# 04-LCD.net
KiCad netlist of a schematic drawn in Altium Designer
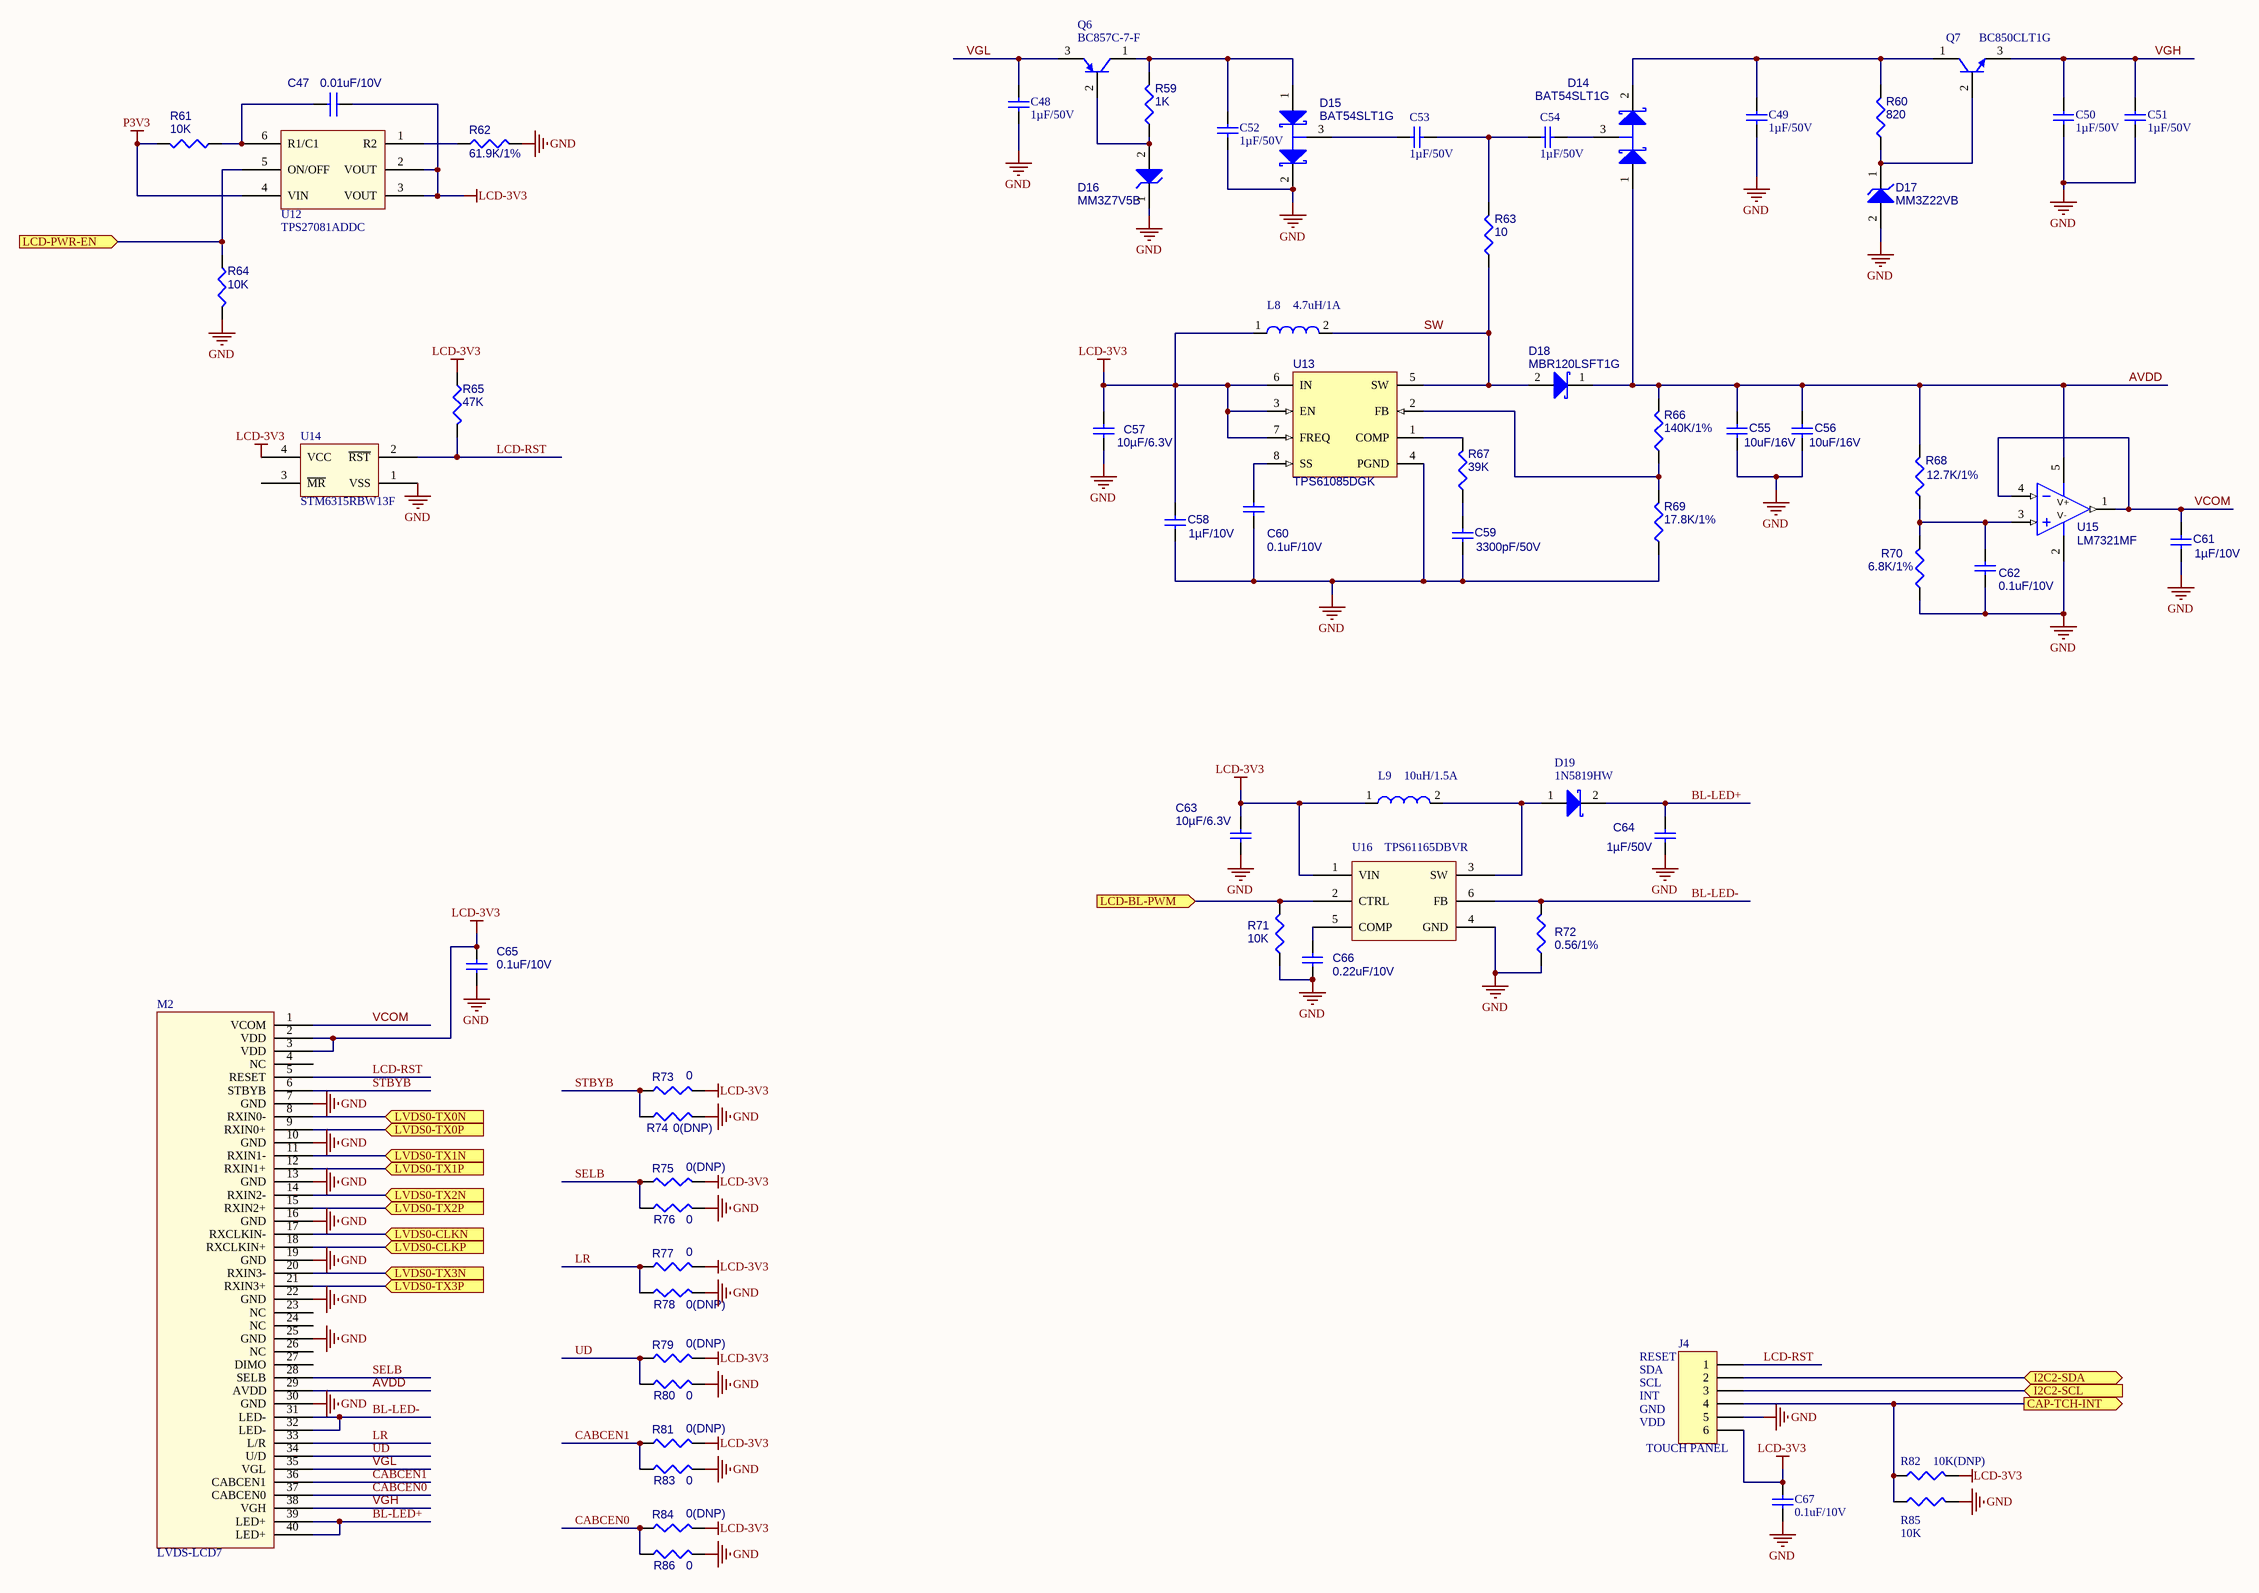
[diagram p0: 04-LCD.SchDoc]

(export (version "E")
  (design (tool "Eeschema 10.0.6"))
  (components
    (comp (ref "C47") (value "0.01uF/10V") (footprint "0402") (libsource (lib "*") (part "P_CAP NP")))
    (comp (ref "C48")
      (value "1µF/50V")
      (footprint "0603")
      (description "Capacitor")
      (fields (field (name "PUBLISHER") "Altium Limited"))
      (libsource (lib "Miscellaneous Devices") (part "Cap"))
    )
    (comp (ref "C49")
      (value "1µF/50V")
      (footprint "0603")
      (description "Capacitor")
      (fields (field (name "PUBLISHER") "Altium Limited"))
      (libsource (lib "Miscellaneous Devices") (part "Cap"))
    )
    (comp (ref "C50")
      (value "1µF/50V")
      (footprint "0603")
      (description "Capacitor")
      (fields (field (name "PUBLISHER") "Altium Limited"))
      (libsource (lib "Miscellaneous Devices") (part "Cap"))
    )
    (comp (ref "C51")
      (value "1µF/50V")
      (footprint "0603")
      (description "Capacitor")
      (fields (field (name "PUBLISHER") "Altium Limited"))
      (libsource (lib "Miscellaneous Devices") (part "Cap"))
    )
    (comp (ref "C52")
      (value "1µF/50V")
      (footprint "0603")
      (description "Capacitor")
      (fields (field (name "PUBLISHER") "Altium Limited"))
      (libsource (lib "Miscellaneous Devices") (part "Cap"))
    )
    (comp (ref "C53")
      (value "1µF/50V")
      (footprint "0603")
      (description "Capacitor")
      (fields (field (name "PUBLISHER") "Altium Limited"))
      (libsource (lib "Miscellaneous Devices") (part "Cap"))
    )
    (comp (ref "C54")
      (value "1µF/50V")
      (footprint "0603")
      (description "Capacitor")
      (fields (field (name "PUBLISHER") "Altium Limited"))
      (libsource (lib "Miscellaneous Devices") (part "Cap"))
    )
    (comp (ref "C55")
      (value "10uF/16V")
      (footprint "0805")
      (description "CAP, CERM, 10 µF, 25 V, +/- 10%, X5R, 0805")
      (fields
        (field (name "PARTNUMBER") "C2012X5R1E106K125AB")
        (field (name "MANUFACTURER") "TDK")
        (field (name "PUBLISHER") "Texas Instruments")
      )
      (libsource (lib "Capacitor_Ceramic") (part "C2012X5R1E106K125AB"))
    )
    (comp (ref "C56")
      (value "10uF/16V")
      (footprint "0805")
      (description "CAP, CERM, 10 µF, 25 V, +/- 10%, X5R, 0805")
      (fields
        (field (name "PARTNUMBER") "C2012X5R1E106K125AB")
        (field (name "MANUFACTURER") "TDK")
        (field (name "PUBLISHER") "Texas Instruments")
      )
      (libsource (lib "Capacitor_Ceramic") (part "C2012X5R1E106K125AB"))
    )
    (comp (ref "C57")
      (value "10µF/6.3V")
      (footprint "0805")
      (description "CAP, CERM, 10 µF, 10 V, +/- 10%, X5R, 0805")
      (fields
        (field (name "PARTNUMBER") "GRM219R61A106KE44D")
        (field (name "MANUFACTURER") "MuRata")
        (field (name "PUBLISHER") "Texas Instruments")
      )
      (libsource (lib "Capacitor_Ceramic") (part "GRM219R61A106KE44D"))
    )
    (comp (ref "C58")
      (value "1µF/10V")
      (footprint "0402")
      (description "CAP, CERM, 1 µF, 50 V, +/- 10%, X5R, 0603")
      (fields
        (field (name "PARTNUMBER") "GRM188R61H105KAALD")
        (field (name "MANUFACTURER") "MuRata")
        (field (name "PUBLISHER") "Texas Instruments")
      )
      (libsource (lib "Capacitor_Ceramic") (part "GRM188R61H105KAALD"))
    )
    (comp (ref "C59")
      (value "3300pF/50V")
      (footprint "0402")
      (description "CAP, CERM, 3300 pF, 50 V, +/- 10%, X7R, 0402")
      (fields
        (field (name "PARTNUMBER") "GRM155R71H332KA01D")
        (field (name "MANUFACTURER") "MuRata")
        (field (name "PUBLISHER") "Texas Instruments")
      )
      (libsource (lib "Capacitor_Ceramic") (part "GRM155R71H332KA01D"))
    )
    (comp (ref "C60")
      (value "0.1uF/10V")
      (footprint "0402")
      (description "CAP, CERM, 0.1 µF, 16 V, +/- 10%, X7R, 0402")
      (fields
        (field (name "PARTNUMBER") "GRM155R71C104KA88D")
        (field (name "MANUFACTURER") "MuRata")
        (field (name "PUBLISHER") "Texas Instruments")
      )
      (libsource (lib "Capacitor_Ceramic") (part "GRM155R71C104KA88D"))
    )
    (comp (ref "C61")
      (value "1µF/10V")
      (footprint "0402")
      (description "CAP, CERM, 1 µF, 50 V, +/- 10%, X5R, 0603")
      (fields
        (field (name "PARTNUMBER") "GRM188R61H105KAALD")
        (field (name "MANUFACTURER") "MuRata")
        (field (name "PUBLISHER") "Texas Instruments")
      )
      (libsource (lib "Capacitor_Ceramic") (part "GRM188R61H105KAALD"))
    )
    (comp (ref "C62")
      (value "0.1uF/10V")
      (footprint "0402")
      (description "CAP, CERM, 0.1 µF, 16 V, +/- 10%, X7R, 0402")
      (fields
        (field (name "PARTNUMBER") "GRM155R71C104KA88D")
        (field (name "MANUFACTURER") "MuRata")
        (field (name "PUBLISHER") "Texas Instruments")
      )
      (libsource (lib "Capacitor_Ceramic") (part "GRM155R71C104KA88D"))
    )
    (comp (ref "C63")
      (value "10µF/6.3V")
      (footprint "0805")
      (description "CAP, CERM, 10 µF, 10 V, +/- 10%, X5R, 0805")
      (fields
        (field (name "PARTNUMBER") "GRM219R61A106KE44D")
        (field (name "MANUFACTURER") "MuRata")
        (field (name "PUBLISHER") "Texas Instruments")
      )
      (libsource (lib "Capacitor_Ceramic") (part "GRM219R61A106KE44D"))
    )
    (comp (ref "C64")
      (value "1µF/50V")
      (footprint "0603")
      (description "CAP, CERM, 1 µF, 50 V, +/- 10%, X5R, 0603")
      (fields
        (field (name "PARTNUMBER") "GRM188R61H105KAALD")
        (field (name "MANUFACTURER") "MuRata")
        (field (name "PUBLISHER") "Texas Instruments")
      )
      (libsource (lib "Capacitor_Ceramic") (part "GRM188R61H105KAALD"))
    )
    (comp (ref "C65")
      (value "0.1uF/10V")
      (footprint "0402")
      (description "CAP, CERM, 0.1 µF, 16 V, +/- 10%, X7R, 0402")
      (fields
        (field (name "PARTNUMBER") "GRM155R71C104KA88D")
        (field (name "MANUFACTURER") "MuRata")
        (field (name "PUBLISHER") "Texas Instruments")
      )
      (libsource (lib "Capacitor_Ceramic") (part "GRM155R71C104KA88D"))
    )
    (comp (ref "C66")
      (value "0.22uF/10V")
      (footprint "0402")
      (description "CAP, CERM, 0.1 µF, 16 V, +/- 10%, X7R, 0402")
      (fields
        (field (name "PARTNUMBER") "GRM155R71C104KA88D")
        (field (name "MANUFACTURER") "MuRata")
        (field (name "PUBLISHER") "Texas Instruments")
      )
      (libsource (lib "Capacitor_Ceramic") (part "GRM155R71C104KA88D"))
    )
    (comp (ref "C67")
      (value "0.1uF/10V")
      (footprint "0402")
      (description "Capacitor")
      (fields (field (name "PUBLISHER") "Altium Limited"))
      (libsource (lib "Miscellaneous Devices") (part "Cap"))
    )
    (comp (ref "D14")
      (value "BAT54SLT1G")
      (footprint "SOT-23")
      (description "Diode, Schottky, 30 V, 0.2 A, SOT-23")
      (fields (field (name "MANUFACTURER") "ON Semiconductor") (field (name "PUBLISHER") "Texas Instruments"))
      (libsource (lib "Diode") (part "BAT54SLT1G"))
    )
    (comp (ref "D15")
      (value "BAT54SLT1G")
      (footprint "SOT-23")
      (description "Diode, Schottky, 30 V, 0.2 A, SOT-23")
      (fields (field (name "MANUFACTURER") "ON Semiconductor") (field (name "PUBLISHER") "Texas Instruments"))
      (libsource (lib "Diode") (part "BAT54SLT1G"))
    )
    (comp (ref "D16")
      (value "MM3Z7V5B")
      (footprint "SOD323F")
      (description "Diode, Zener, 7.5 V, 200 mW, SOD-323F")
      (fields
        (field (name "MANUFACTURER") "Fairchild Semiconductor")
        (field (name "SYMBOLCREATOR") "a0412235")
        (field (name "PUBLISHER") "Texas Instruments")
      )
      (libsource (lib "ZenerDiodes") (part "MM3Z7V5B"))
    )
    (comp (ref "D17")
      (value "MM3Z22VB")
      (footprint "SOD323F")
      (description "Diode, Zener, 18 V, 200 mW, SOD-323F")
      (fields
        (field (name "PARTNUMBER") "MM3Z18VB")
        (field (name "MANUFACTURER") "Fairchild Semiconductor")
        (field (name "SYMBOLCREATOR") "a0412235")
        (field (name "PUBLISHER") "Texas Instruments")
      )
      (libsource (lib "ZenerDiodes") (part "MM3Z18VB"))
    )
    (comp (ref "D18")
      (value "MBR120LSFT1G")
      (footprint "SOD123FL")
      (description "Diode, Schottky, 20 V, 1 A, SOD-123FL")
      (fields (field (name "MANUFACTURER") "ON Semiconductor") (field (name "PUBLISHER") "Texas Instruments"))
      (libsource (lib "Diode") (part "MBR120LSFT1G"))
    )
    (comp (ref "D19")
      (value "1N5819HW")
      (footprint "1N5819")
      (description "Schottky Rectifier")
      (libsource (lib "Miscellaneous Devices") (part "Diode 11DQ03"))
    )
    (comp (ref "J4")
      (value "TOUCH PANEL")
      (footprint "FPC0.5-DR-SMD-XP-F(6P)")
      (description "Header, 6-Pin")
      (fields (field (name "PUBLISHER") "Altium Limited"))
      (libsource (lib "Miscellaneous Connectors") (part "Header 6"))
    )
    (comp (ref "L8")
      (value "4.7uH/1A")
      (footprint "IND-4.7UH-1A")
      (description "IND PWR 4.7UH@1MHZ 1A 20% SMD")
      (fields (field (name "TOLERANCE") "20%"))
      (libsource (lib "*") (part "INDUCTOR"))
    )
    (comp (ref "L9")
      (value "10uH/1.5A")
      (footprint "IND-10UH-1.5A")
      (description "IND PWR 4.7UH@1MHZ 1A 20% SMD")
      (fields (field (name "TOLERANCE") "20%"))
      (libsource (lib "*") (part "INDUCTOR"))
    )
    (comp (ref "M2")
      (value "LVDS-LCD7")
      (footprint "FPC0.5-DR-SMD-XP-F(40P)")
      (libsource (lib "Schlib") (part "LVDS-LCD7"))
    )
    (comp (ref "Q6")
      (value "BC857C-7-F")
      (footprint "NPN")
      (description "PNP Bipolar Transistor")
      (fields (field (name "PUBLISHER") "Altium Limited"))
      (libsource (lib "Miscellaneous Devices") (part "PNP"))
    )
    (comp (ref "Q7")
      (value "BC850CLT1G")
      (footprint "NPN")
      (description "NPN Bipolar Transistor")
      (fields (field (name "PUBLISHER") "Altium Limited"))
      (libsource (lib "Miscellaneous Devices") (part "NPN"))
    )
    (comp (ref "R59") (value "1K") (footprint "0603") (libsource (lib "*") (part "P_R")))
    (comp (ref "R60") (value "820") (footprint "0603") (libsource (lib "*") (part "P_R")))
    (comp (ref "R61") (value "10K") (footprint "0402") (libsource (lib "*") (part "P_R")))
    (comp (ref "R62") (value "61.9K/1%") (footprint "0402") (libsource (lib "*") (part "P_R")))
    (comp (ref "R63") (value "10") (footprint "0603") (libsource (lib "*") (part "P_R")))
    (comp (ref "R64") (value "10K") (footprint "0402") (libsource (lib "*") (part "P_R")))
    (comp (ref "R65") (value "47K") (footprint "0402") (libsource (lib "*") (part "P_R")))
    (comp (ref "R66") (value "140K/1%") (footprint "0402") (libsource (lib "*") (part "P_R")))
    (comp (ref "R67") (value "39K") (footprint "0402") (libsource (lib "*") (part "P_R")))
    (comp (ref "R68") (value "12.7K/1%") (footprint "0402") (libsource (lib "*") (part "P_R")))
    (comp (ref "R69") (value "17.8K/1%") (footprint "0402") (libsource (lib "*") (part "P_R")))
    (comp (ref "R70") (value "6.8K/1%") (footprint "0402") (libsource (lib "*") (part "P_R")))
    (comp (ref "R71") (value "10K") (footprint "0402") (libsource (lib "*") (part "P_R")))
    (comp (ref "R72") (value "0.56/1%") (footprint "0805") (libsource (lib "*") (part "P_R")))
    (comp (ref "R73") (value "0") (footprint "0402") (libsource (lib "*") (part "P_R")))
    (comp (ref "R74") (value "0(DNP)") (footprint "0402") (libsource (lib "*") (part "P_R")))
    (comp (ref "R75") (value "0(DNP)") (footprint "0402") (libsource (lib "*") (part "P_R")))
    (comp (ref "R76") (value "0") (footprint "0402") (libsource (lib "*") (part "P_R")))
    (comp (ref "R77") (value "0") (footprint "0402") (libsource (lib "*") (part "P_R")))
    (comp (ref "R78") (value "0(DNP)") (footprint "0402") (libsource (lib "*") (part "P_R")))
    (comp (ref "R79") (value "0(DNP)") (footprint "0402") (libsource (lib "*") (part "P_R")))
    (comp (ref "R80") (value "0") (footprint "0402") (libsource (lib "*") (part "P_R")))
    (comp (ref "R81") (value "0(DNP)") (footprint "0402") (libsource (lib "*") (part "P_R")))
    (comp (ref "R82") (value "10K(DNP)") (footprint "0402") (libsource (lib "*") (part "CR16-1003FM")))
    (comp (ref "R83") (value "0") (footprint "0402") (libsource (lib "*") (part "P_R")))
    (comp (ref "R84") (value "0(DNP)") (footprint "0402") (libsource (lib "*") (part "P_R")))
    (comp (ref "R85") (value "10K") (footprint "0402") (libsource (lib "*") (part "CR16-1003FM")))
    (comp (ref "R86") (value "0") (footprint "0402") (libsource (lib "*") (part "P_R")))
    (comp (ref "U12")
      (value "TPS27081ADDC")
      (footprint "SOT23-6")
      (libsource (lib "Schlib") (part "TPS27081A"))
    )
    (comp (ref "U13")
      (value "TPS61085DGK")
      (footprint "MSOP")
      (fields
        (field (name "MANUFACTURER") "Texas Instruments")
        (field (name "ALTERNATE PARTNUMBER") "Equivalent")
      )
      (libsource (lib "TI Power Management Lighting and Display") (part "TPS61085DGKR"))
    )
    (comp (ref "U14")
      (value "STM6315RBW13F")
      (footprint "SOT143-4")
      (libsource (lib "Schlib") (part "STM6315"))
    )
    (comp (ref "U15")
      (value "LM7321MF")
      (footprint "SOT23-5")
      (description "Single 30V High Output Current and Unlimited Capacitive Load Op Amp")
      (fields
        (field (name "MANUFACTURER") "National Semiconductor")
        (field (name "PUBLISHER") "National Semiconductor")
      )
      (libsource (lib "NSC Amplifier") (part "LM7321MF"))
    )
    (comp (ref "U16")
      (value "TPS61165DBVR")
      (footprint "SOT23-6")
      (libsource (lib "Schlib") (part "TPS61165DBVR"))
    )
  )
  (nets
    (net (code "1") (name "/AVDD") (class "Default")
      (node (ref "C55") (pin "1") (pinfunction "1_1") (pintype "passive"))
      (node (ref "C56") (pin "1") (pinfunction "1_1") (pintype "passive"))
      (node (ref "D14") (pin "1") (pinfunction "A_1") (pintype "passive"))
      (node (ref "D18") (pin "1") (pinfunction "K_1") (pintype "passive"))
      (node (ref "M2") (pin "29") (pinfunction "AVDD_29") (pintype "passive"))
      (node (ref "R66") (pin "1") (pinfunction "1_1") (pintype "passive"))
      (node (ref "R68") (pin "1") (pinfunction "1_1") (pintype "passive"))
      (node (ref "U15") (pin "5") (pinfunction "V+_5") (pintype "power_in"))
    )
    (net (code "2") (name "/BL-LED+") (class "Default")
      (node (ref "C64") (pin "1") (pinfunction "1_1") (pintype "passive"))
      (node (ref "D19") (pin "2") (pinfunction "K_2") (pintype "passive"))
      (node (ref "M2") (pin "39") (pinfunction "LED+_39") (pintype "passive"))
      (node (ref "M2") (pin "40") (pinfunction "LED+_40") (pintype "passive"))
    )
    (net (code "3") (name "/BL-LED-") (class "Default")
      (node (ref "M2") (pin "31") (pinfunction "LED-_31") (pintype "passive"))
      (node (ref "M2") (pin "32") (pinfunction "LED-_32") (pintype "passive"))
      (node (ref "R72") (pin "1") (pinfunction "1_1") (pintype "passive"))
      (node (ref "U16") (pin "6") (pinfunction "FB_6") (pintype "passive"))
    )
    (net (code "4") (name "/CABCEN0") (class "Default")
      (node (ref "M2") (pin "37") (pinfunction "CABCEN0_37") (pintype "passive"))
      (node (ref "R84") (pin "2") (pinfunction "2_2") (pintype "passive"))
      (node (ref "R86") (pin "2") (pinfunction "2_2") (pintype "passive"))
    )
    (net (code "5") (name "/CABCEN1") (class "Default")
      (node (ref "M2") (pin "36") (pinfunction "CABCEN1_36") (pintype "passive"))
      (node (ref "R81") (pin "2") (pinfunction "2_2") (pintype "passive"))
      (node (ref "R83") (pin "2") (pinfunction "2_2") (pintype "passive"))
    )
    (net (code "6") (name "/CAP-TCH-INT") (class "Default")
      (node (ref "J4") (pin "4") (pinfunction "4_4") (pintype "passive"))
      (node (ref "R82") (pin "1") (pinfunction "1_1") (pintype "passive"))
      (node (ref "R85") (pin "1") (pinfunction "1_1") (pintype "passive"))
    )
    (net (code "7") (name "/I2C2-SCL") (class "Default")
      (node (ref "J4") (pin "3") (pinfunction "3_3") (pintype "passive"))
    )
    (net (code "8") (name "/I2C2-SDA") (class "Default")
      (node (ref "J4") (pin "2") (pinfunction "2_2") (pintype "passive"))
    )
    (net (code "9") (name "/LCD-BL-PWM") (class "Default")
      (node (ref "R71") (pin "1") (pinfunction "1_1") (pintype "passive"))
      (node (ref "U16") (pin "2") (pinfunction "CTRL_2") (pintype "passive"))
    )
    (net (code "10") (name "/LCD-PWR-EN") (class "Default")
      (node (ref "R64") (pin "2") (pinfunction "2_2") (pintype "passive"))
      (node (ref "U12") (pin "5") (pinfunction "ON/OFF_5") (pintype "passive"))
    )
    (net (code "11") (name "/LCD-RST") (class "Default")
      (node (ref "J4") (pin "1") (pinfunction "1_1") (pintype "passive"))
      (node (ref "M2") (pin "5") (pinfunction "RESET_5") (pintype "passive"))
      (node (ref "R65") (pin "1") (pinfunction "1_1") (pintype "passive"))
      (node (ref "U14") (pin "2") (pinfunction "~{RST}_2") (pintype "passive"))
    )
    (net (code "12") (name "/LR") (class "Default")
      (node (ref "M2") (pin "33") (pinfunction "L/R_33") (pintype "passive"))
      (node (ref "R77") (pin "2") (pinfunction "2_2") (pintype "passive"))
      (node (ref "R78") (pin "2") (pinfunction "2_2") (pintype "passive"))
    )
    (net (code "13") (name "/LVDS0-CLKN") (class "Default")
      (node (ref "M2") (pin "17") (pinfunction "RXCLKIN-_17") (pintype "passive"))
    )
    (net (code "14") (name "/LVDS0-CLKP") (class "Default")
      (node (ref "M2") (pin "18") (pinfunction "RXCLKIN+_18") (pintype "passive"))
    )
    (net (code "15") (name "/LVDS0-TX0N") (class "Default")
      (node (ref "M2") (pin "8") (pinfunction "RXIN0-_8") (pintype "passive"))
    )
    (net (code "16") (name "/LVDS0-TX0P") (class "Default")
      (node (ref "M2") (pin "9") (pinfunction "RXIN0+_9") (pintype "passive"))
    )
    (net (code "17") (name "/LVDS0-TX1N") (class "Default")
      (node (ref "M2") (pin "11") (pinfunction "RXIN1-_11") (pintype "passive"))
    )
    (net (code "18") (name "/LVDS0-TX1P") (class "Default")
      (node (ref "M2") (pin "12") (pinfunction "RXIN1+_12") (pintype "passive"))
    )
    (net (code "19") (name "/LVDS0-TX2N") (class "Default")
      (node (ref "M2") (pin "14") (pinfunction "RXIN2-_14") (pintype "passive"))
    )
    (net (code "20") (name "/LVDS0-TX2P") (class "Default")
      (node (ref "M2") (pin "15") (pinfunction "RXIN2+_15") (pintype "passive"))
    )
    (net (code "21") (name "/LVDS0-TX3N") (class "Default")
      (node (ref "M2") (pin "20") (pinfunction "RXIN3-_20") (pintype "passive"))
    )
    (net (code "22") (name "/LVDS0-TX3P") (class "Default")
      (node (ref "M2") (pin "21") (pinfunction "RXIN3+_21") (pintype "passive"))
    )
    (net (code "23") (name "/SELB") (class "Default")
      (node (ref "M2") (pin "28") (pinfunction "SELB_28") (pintype "passive"))
      (node (ref "R75") (pin "2") (pinfunction "2_2") (pintype "passive"))
      (node (ref "R76") (pin "2") (pinfunction "2_2") (pintype "passive"))
    )
    (net (code "24") (name "/STBYB") (class "Default")
      (node (ref "M2") (pin "6") (pinfunction "STBYB_6") (pintype "passive"))
      (node (ref "R73") (pin "2") (pinfunction "2_2") (pintype "passive"))
      (node (ref "R74") (pin "2") (pinfunction "2_2") (pintype "passive"))
    )
    (net (code "25") (name "/SW") (class "Default")
      (node (ref "D18") (pin "2") (pinfunction "A_2") (pintype "passive"))
      (node (ref "L8") (pin "2") (pinfunction "2_2") (pintype "passive"))
      (node (ref "R63") (pin "2") (pinfunction "2_2") (pintype "passive"))
      (node (ref "U13") (pin "5") (pinfunction "SW_5") (pintype "power_in"))
    )
    (net (code "26") (name "/UD") (class "Default")
      (node (ref "M2") (pin "34") (pinfunction "U/D_34") (pintype "passive"))
      (node (ref "R79") (pin "2") (pinfunction "2_2") (pintype "passive"))
      (node (ref "R80") (pin "2") (pinfunction "2_2") (pintype "passive"))
    )
    (net (code "27") (name "/VCOM") (class "Default")
      (node (ref "C61") (pin "1") (pinfunction "1_1") (pintype "passive"))
      (node (ref "M2") (pin "1") (pinfunction "VCOM_1") (pintype "passive"))
      (node (ref "U15") (pin "1") (pinfunction "OUT_1") (pintype "output"))
      (node (ref "U15") (pin "4") (pinfunction "IN-_4") (pintype "input"))
    )
    (net (code "28") (name "/VGH") (class "Default")
      (node (ref "C50") (pin "1") (pinfunction "1_1") (pintype "passive"))
      (node (ref "C51") (pin "1") (pinfunction "1_1") (pintype "passive"))
      (node (ref "M2") (pin "38") (pinfunction "VGH_38") (pintype "passive"))
      (node (ref "Q7") (pin "3") (pinfunction "E_3") (pintype "passive"))
    )
    (net (code "29") (name "/VGL") (class "Default")
      (node (ref "C48") (pin "2") (pinfunction "2_2") (pintype "passive"))
      (node (ref "M2") (pin "35") (pinfunction "VGL_35") (pintype "passive"))
      (node (ref "Q6") (pin "3") (pinfunction "E_3") (pintype "passive"))
    )
    (net (code "30") (name "GND") (class "Default")
      (node (ref "C48") (pin "1") (pinfunction "1_1") (pintype "passive"))
      (node (ref "C49") (pin "2") (pinfunction "2_2") (pintype "passive"))
      (node (ref "C50") (pin "2") (pinfunction "2_2") (pintype "passive"))
      (node (ref "C51") (pin "2") (pinfunction "2_2") (pintype "passive"))
      (node (ref "C52") (pin "2") (pinfunction "2_2") (pintype "passive"))
      (node (ref "C55") (pin "2") (pinfunction "2_2") (pintype "passive"))
      (node (ref "C56") (pin "2") (pinfunction "2_2") (pintype "passive"))
      (node (ref "C57") (pin "2") (pinfunction "2_2") (pintype "passive"))
      (node (ref "C58") (pin "2") (pinfunction "2_2") (pintype "passive"))
      (node (ref "C59") (pin "2") (pinfunction "2_2") (pintype "passive"))
      (node (ref "C60") (pin "2") (pinfunction "2_2") (pintype "passive"))
      (node (ref "C61") (pin "2") (pinfunction "2_2") (pintype "passive"))
      (node (ref "C62") (pin "2") (pinfunction "2_2") (pintype "passive"))
      (node (ref "C63") (pin "2") (pinfunction "2_2") (pintype "passive"))
      (node (ref "C64") (pin "2") (pinfunction "2_2") (pintype "passive"))
      (node (ref "C65") (pin "2") (pinfunction "2_2") (pintype "passive"))
      (node (ref "C66") (pin "2") (pinfunction "2_2") (pintype "passive"))
      (node (ref "C67") (pin "2") (pinfunction "2_2") (pintype "passive"))
      (node (ref "D15") (pin "2") (pinfunction "K_2") (pintype "passive"))
      (node (ref "D16") (pin "1") (pinfunction "K_1") (pintype "passive"))
      (node (ref "D17") (pin "2") (pinfunction "A_2") (pintype "passive"))
      (node (ref "J4") (pin "5") (pinfunction "5_5") (pintype "passive"))
      (node (ref "M2") (pin "10") (pinfunction "GND_10") (pintype "passive"))
      (node (ref "M2") (pin "13") (pinfunction "GND_13") (pintype "passive"))
      (node (ref "M2") (pin "16") (pinfunction "GND_16") (pintype "passive"))
      (node (ref "M2") (pin "19") (pinfunction "GND_19") (pintype "passive"))
      (node (ref "M2") (pin "22") (pinfunction "GND_22") (pintype "passive"))
      (node (ref "M2") (pin "25") (pinfunction "GND_25") (pintype "passive"))
      (node (ref "M2") (pin "30") (pinfunction "GND_30") (pintype "passive"))
      (node (ref "M2") (pin "7") (pinfunction "GND_7") (pintype "passive"))
      (node (ref "R62") (pin "1") (pinfunction "1_1") (pintype "passive"))
      (node (ref "R64") (pin "1") (pinfunction "1_1") (pintype "passive"))
      (node (ref "R69") (pin "2") (pinfunction "2_2") (pintype "passive"))
      (node (ref "R70") (pin "2") (pinfunction "2_2") (pintype "passive"))
      (node (ref "R71") (pin "2") (pinfunction "2_2") (pintype "passive"))
      (node (ref "R72") (pin "2") (pinfunction "2_2") (pintype "passive"))
      (node (ref "R74") (pin "1") (pinfunction "1_1") (pintype "passive"))
      (node (ref "R76") (pin "1") (pinfunction "1_1") (pintype "passive"))
      (node (ref "R78") (pin "1") (pinfunction "1_1") (pintype "passive"))
      (node (ref "R80") (pin "1") (pinfunction "1_1") (pintype "passive"))
      (node (ref "R83") (pin "1") (pinfunction "1_1") (pintype "passive"))
      (node (ref "R85") (pin "2") (pinfunction "2_2") (pintype "passive"))
      (node (ref "R86") (pin "1") (pinfunction "1_1") (pintype "passive"))
      (node (ref "U13") (pin "4") (pinfunction "PGND_4") (pintype "power_in"))
      (node (ref "U14") (pin "1") (pinfunction "VSS_1") (pintype "passive"))
      (node (ref "U15") (pin "2") (pinfunction "V-_2") (pintype "power_in"))
      (node (ref "U16") (pin "4") (pinfunction "GND_4") (pintype "passive"))
    )
    (net (code "31") (name "LCD-3V3") (class "Default")
      (node (ref "C47") (pin "1") (pinfunction "1_1") (pintype "passive"))
      (node (ref "C57") (pin "1") (pinfunction "1_1") (pintype "passive"))
      (node (ref "C58") (pin "1") (pinfunction "1_1") (pintype "passive"))
      (node (ref "C63") (pin "1") (pinfunction "1_1") (pintype "passive"))
      (node (ref "C65") (pin "1") (pinfunction "1_1") (pintype "passive"))
      (node (ref "C67") (pin "1") (pinfunction "1_1") (pintype "passive"))
      (node (ref "J4") (pin "6") (pinfunction "6_6") (pintype "passive"))
      (node (ref "L8") (pin "1") (pinfunction "1_1") (pintype "passive"))
      (node (ref "L9") (pin "1") (pinfunction "1_1") (pintype "passive"))
      (node (ref "M2") (pin "2") (pinfunction "VDD_2") (pintype "passive"))
      (node (ref "M2") (pin "3") (pinfunction "VDD_3") (pintype "passive"))
      (node (ref "R65") (pin "2") (pinfunction "2_2") (pintype "passive"))
      (node (ref "R73") (pin "1") (pinfunction "1_1") (pintype "passive"))
      (node (ref "R75") (pin "1") (pinfunction "1_1") (pintype "passive"))
      (node (ref "R77") (pin "1") (pinfunction "1_1") (pintype "passive"))
      (node (ref "R79") (pin "1") (pinfunction "1_1") (pintype "passive"))
      (node (ref "R81") (pin "1") (pinfunction "1_1") (pintype "passive"))
      (node (ref "R82") (pin "2") (pinfunction "2_2") (pintype "passive"))
      (node (ref "R84") (pin "1") (pinfunction "1_1") (pintype "passive"))
      (node (ref "U12") (pin "2") (pinfunction "VOUT_2") (pintype "passive"))
      (node (ref "U12") (pin "3") (pinfunction "VOUT_3") (pintype "passive"))
      (node (ref "U13") (pin "3") (pinfunction "EN_3") (pintype "input"))
      (node (ref "U13") (pin "6") (pinfunction "IN_6") (pintype "power_in"))
      (node (ref "U13") (pin "7") (pinfunction "FREQ_7") (pintype "input"))
      (node (ref "U14") (pin "4") (pinfunction "VCC_4") (pintype "passive"))
      (node (ref "U16") (pin "1") (pinfunction "VIN_1") (pintype "passive"))
    )
    (net (code "32") (name "Net-(C53-Pad1)") (class "Default")
      (node (ref "C53") (pin "1") (pinfunction "1_1") (pintype "passive"))
      (node (ref "C54") (pin "2") (pinfunction "2_2") (pintype "passive"))
      (node (ref "R63") (pin "1") (pinfunction "1_1") (pintype "passive"))
    )
    (net (code "33") (name "Net-(C59-Pad1)") (class "Default")
      (node (ref "C59") (pin "1") (pinfunction "1_1") (pintype "passive"))
      (node (ref "R67") (pin "2") (pinfunction "2_2") (pintype "passive"))
    )
    (net (code "34") (name "Net-(D14-C)") (class "Default")
      (node (ref "C54") (pin "1") (pinfunction "1_1") (pintype "passive"))
      (node (ref "D14") (pin "3") (pinfunction "C_3") (pintype "passive"))
    )
    (net (code "35") (name "Net-(D14-K)") (class "Default")
      (node (ref "C49") (pin "1") (pinfunction "1_1") (pintype "passive"))
      (node (ref "D14") (pin "2") (pinfunction "K_2") (pintype "passive"))
      (node (ref "Q7") (pin "1") (pinfunction "C_1") (pintype "passive"))
      (node (ref "R60") (pin "1") (pinfunction "1_1") (pintype "passive"))
    )
    (net (code "36") (name "Net-(D15-A)") (class "Default")
      (node (ref "C52") (pin "1") (pinfunction "1_1") (pintype "passive"))
      (node (ref "D15") (pin "1") (pinfunction "A_1") (pintype "passive"))
      (node (ref "Q6") (pin "1") (pinfunction "C_1") (pintype "passive"))
      (node (ref "R59") (pin "1") (pinfunction "1_1") (pintype "passive"))
    )
    (net (code "37") (name "Net-(D15-C)") (class "Default")
      (node (ref "C53") (pin "2") (pinfunction "2_2") (pintype "passive"))
      (node (ref "D15") (pin "3") (pinfunction "C_3") (pintype "passive"))
    )
    (net (code "38") (name "Net-(D16-A)") (class "Default")
      (node (ref "D16") (pin "2") (pinfunction "A_2") (pintype "passive"))
      (node (ref "Q6") (pin "2") (pinfunction "B_2") (pintype "passive"))
      (node (ref "R59") (pin "2") (pinfunction "2_2") (pintype "passive"))
    )
    (net (code "39") (name "Net-(D17-K)") (class "Default")
      (node (ref "D17") (pin "1") (pinfunction "K_1") (pintype "passive"))
      (node (ref "Q7") (pin "2") (pinfunction "B_2") (pintype "passive"))
      (node (ref "R60") (pin "2") (pinfunction "2_2") (pintype "passive"))
    )
    (net (code "40") (name "Net-(D19-A)") (class "Default")
      (node (ref "D19") (pin "1") (pinfunction "A_1") (pintype "passive"))
      (node (ref "L9") (pin "2") (pinfunction "2_2") (pintype "passive"))
      (node (ref "U16") (pin "3") (pinfunction "SW_3") (pintype "passive"))
    )
    (net (code "41") (name "Net-(U12-R1{slash}C1)") (class "Default")
      (node (ref "C47") (pin "2") (pinfunction "2_2") (pintype "passive"))
      (node (ref "R61") (pin "2") (pinfunction "2_2") (pintype "passive"))
      (node (ref "U12") (pin "6") (pinfunction "R1/C1_6") (pintype "passive"))
    )
    (net (code "42") (name "Net-(U12-R2)") (class "Default")
      (node (ref "R62") (pin "2") (pinfunction "2_2") (pintype "passive"))
      (node (ref "U12") (pin "1") (pinfunction "R2_1") (pintype "passive"))
    )
    (net (code "43") (name "Net-(U13-COMP)") (class "Default")
      (node (ref "R67") (pin "1") (pinfunction "1_1") (pintype "passive"))
      (node (ref "U13") (pin "1") (pinfunction "COMP_1") (pintype "passive"))
    )
    (net (code "44") (name "Net-(U13-FB)") (class "Default")
      (node (ref "R66") (pin "2") (pinfunction "2_2") (pintype "passive"))
      (node (ref "R69") (pin "1") (pinfunction "1_1") (pintype "passive"))
      (node (ref "U13") (pin "2") (pinfunction "FB_2") (pintype "input"))
    )
    (net (code "45") (name "Net-(U13-SS)") (class "Default")
      (node (ref "C60") (pin "1") (pinfunction "1_1") (pintype "passive"))
      (node (ref "U13") (pin "8") (pinfunction "SS_8") (pintype "input"))
    )
    (net (code "46") (name "Net-(U15-IN+)") (class "Default")
      (node (ref "C62") (pin "1") (pinfunction "1_1") (pintype "passive"))
      (node (ref "R68") (pin "2") (pinfunction "2_2") (pintype "passive"))
      (node (ref "R70") (pin "1") (pinfunction "1_1") (pintype "passive"))
      (node (ref "U15") (pin "3") (pinfunction "IN+_3") (pintype "input"))
    )
    (net (code "47") (name "Net-(U16-COMP)") (class "Default")
      (node (ref "C66") (pin "1") (pinfunction "1_1") (pintype "passive"))
      (node (ref "U16") (pin "5") (pinfunction "COMP_5") (pintype "passive"))
    )
    (net (code "48") (name "P3V3") (class "Default")
      (node (ref "R61") (pin "1") (pinfunction "1_1") (pintype "passive"))
      (node (ref "U12") (pin "4") (pinfunction "VIN_4") (pintype "passive"))
    )
    (net (code "49") (name "unconnected-(M2-DIMO-Pad27)") (class "Default")
      (node (ref "M2") (pin "27") (pinfunction "DIMO_27") (pintype "passive"))
    )
    (net (code "50") (name "unconnected-(M2-NC-Pad4)") (class "Default")
      (node (ref "M2") (pin "4") (pinfunction "NC_4") (pintype "passive"))
    )
    (net (code "51") (name "unconnected-(M2-NC-Pad23)") (class "Default")
      (node (ref "M2") (pin "23") (pinfunction "NC_23") (pintype "passive"))
    )
    (net (code "52") (name "unconnected-(M2-NC-Pad24)") (class "Default")
      (node (ref "M2") (pin "24") (pinfunction "NC_24") (pintype "passive"))
    )
    (net (code "53") (name "unconnected-(M2-NC-Pad26)") (class "Default")
      (node (ref "M2") (pin "26") (pinfunction "NC_26") (pintype "passive"))
    )
    (net (code "54") (name "unconnected-(U14-~{MR}-Pad3)") (class "Default")
      (node (ref "U14") (pin "3") (pinfunction "~{MR}_3") (pintype "passive"))
    )
  )
)
